# Pi_grammer_MAIN.net
KiCad netlist of a schematic drawn in EAGLE
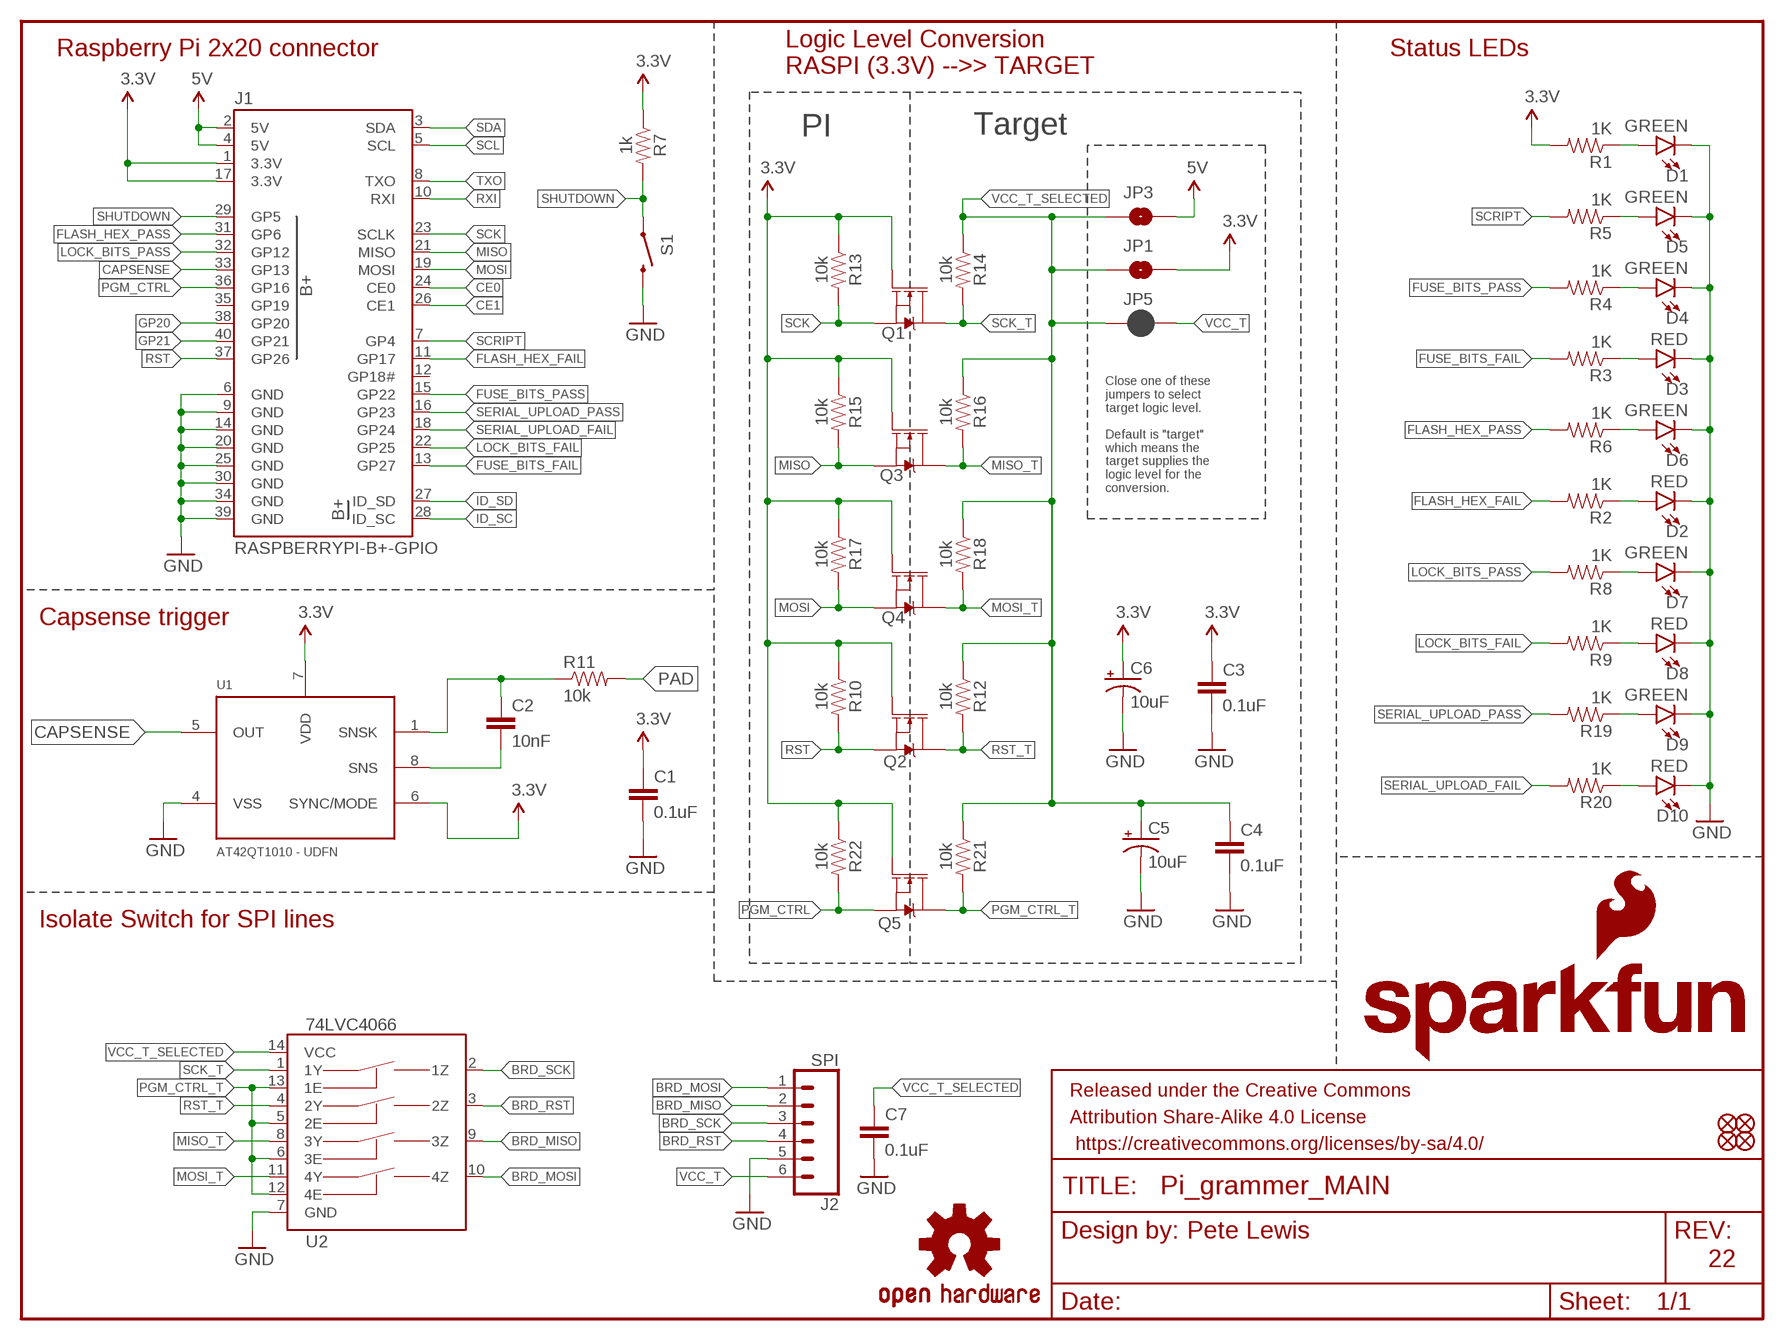
[diagram p0: schematic, sheet 1]

(export (version "E")
  (design (tool "Eeschema 10.0.6"))
  (components
    (comp (ref "C1")
      (value "0.1uF")
      (footprint "eagle-import:0603-CAP")
      (libsource (lib "eagle-import") (part "0.1UF-25V(+80/-20%)(0603)"))
    )
    (comp (ref "C2")
      (value "10nF")
      (footprint "eagle-import:0603-CAP")
      (libsource (lib "eagle-import") (part "10NF/10000PF-50V-10%(0603)"))
    )
    (comp (ref "C3")
      (value "0.1uF")
      (footprint "eagle-import:0603")
      (libsource (lib "eagle-import") (part "0.1UF-0603-25V-(+80/-20%)"))
    )
    (comp (ref "C4")
      (value "0.1uF")
      (footprint "eagle-import:0603")
      (libsource (lib "eagle-import") (part "0.1UF-0603-25V-(+80/-20%)"))
    )
    (comp (ref "C5")
      (value "10uF")
      (footprint "eagle-import:EIA3216")
      (libsource (lib "eagle-import") (part "10UF-POLAR-EIA3216-16V-10%(TANT)"))
    )
    (comp (ref "C6")
      (value "10uF")
      (footprint "eagle-import:EIA3216")
      (libsource (lib "eagle-import") (part "10UF-POLAR-EIA3216-16V-10%(TANT)"))
    )
    (comp (ref "C7")
      (value "0.1uF")
      (footprint "eagle-import:0603")
      (libsource (lib "eagle-import") (part "0.1UF-0603-25V-(+80/-20%)"))
    )
    (comp (ref "D1")
      (value "GREEN")
      (footprint "eagle-import:LED-1206")
      (libsource (lib "eagle-import") (part "LED-GREEN1206"))
    )
    (comp (ref "D2")
      (value "RED")
      (footprint "eagle-import:LED-1206")
      (libsource (lib "eagle-import") (part "LED-RED1206"))
    )
    (comp (ref "D3")
      (value "RED")
      (footprint "eagle-import:LED-1206")
      (libsource (lib "eagle-import") (part "LED-RED1206"))
    )
    (comp (ref "D4")
      (value "GREEN")
      (footprint "eagle-import:LED-1206")
      (libsource (lib "eagle-import") (part "LED-GREEN1206"))
    )
    (comp (ref "D5")
      (value "GREEN")
      (footprint "eagle-import:LED-1206")
      (libsource (lib "eagle-import") (part "LED-GREEN1206"))
    )
    (comp (ref "D6")
      (value "GREEN")
      (footprint "eagle-import:LED-1206")
      (libsource (lib "eagle-import") (part "LED-GREEN1206"))
    )
    (comp (ref "D7")
      (value "GREEN")
      (footprint "eagle-import:LED-1206")
      (libsource (lib "eagle-import") (part "LED-GREEN1206"))
    )
    (comp (ref "D8")
      (value "RED")
      (footprint "eagle-import:LED-1206")
      (libsource (lib "eagle-import") (part "LED-RED1206"))
    )
    (comp (ref "D9")
      (value "GREEN")
      (footprint "eagle-import:LED-1206")
      (libsource (lib "eagle-import") (part "LED-GREEN1206"))
    )
    (comp (ref "D10")
      (value "RED")
      (footprint "eagle-import:LED-1206")
      (libsource (lib "eagle-import") (part "LED-RED1206"))
    )
    (comp (ref "FD1")
      (value "FIDUCIALUFIDUCIAL")
      (footprint "eagle-import:FIDUCIAL-MICRO")
      (libsource (lib "eagle-import") (part "FIDUCIALUFIDUCIAL"))
    )
    (comp (ref "FD2")
      (value "FIDUCIALUFIDUCIAL")
      (footprint "eagle-import:FIDUCIAL-MICRO")
      (libsource (lib "eagle-import") (part "FIDUCIALUFIDUCIAL"))
    )
    (comp (ref "FD3")
      (value "FIDUCIALUFIDUCIAL")
      (footprint "eagle-import:FIDUCIAL-MICRO")
      (libsource (lib "eagle-import") (part "FIDUCIALUFIDUCIAL"))
    )
    (comp (ref "FD4")
      (value "FIDUCIALUFIDUCIAL")
      (footprint "eagle-import:FIDUCIAL-MICRO")
      (libsource (lib "eagle-import") (part "FIDUCIALUFIDUCIAL"))
    )
    (comp (ref "FRAME1")
      (value "FRAME-LETTER")
      (footprint "eagle-import:CREATIVE_COMMONS")
      (libsource (lib "eagle-import") (part "FRAME-LETTER"))
    )
    (comp (ref "J1")
      (value "RASPBERRYPI-B+-GPIO")
      (footprint "eagle-import:2X20-SHROUDED")
      (libsource (lib "eagle-import") (part "RASPBERRYPI-B+-GPIO"))
    )
    (comp (ref "J2")
      (value "SPI")
      (footprint "eagle-import:1X06-SMD_RA_MALE")
      (libsource (lib "eagle-import") (part "CONN_06SMD"))
    )
    (comp (ref "JP1")
      (value "JUMPER-SMT_2_NO_SILK")
      (footprint "eagle-import:SMT-JUMPER_2_NO_SILK")
      (libsource (lib "eagle-import") (part "JUMPER-SMT_2_NO_SILK"))
    )
    (comp (ref "JP3")
      (value "JUMPER-SMT_2_NO_SILK")
      (footprint "eagle-import:SMT-JUMPER_2_NO_SILK")
      (libsource (lib "eagle-import") (part "JUMPER-SMT_2_NO_SILK"))
    )
    (comp (ref "JP5")
      (value "JUMPER-SMT_2_NC_PASTE_SILK")
      (footprint "eagle-import:SMT-JUMPER_2_NC_PASTE_SILK")
      (libsource (lib "eagle-import") (part "JUMPER-SMT_2_NC_PASTE_SILK"))
    )
    (comp (ref "LOGO1")
      (value "SFE_LOGO_FLAME.2_INCH")
      (footprint "eagle-import:SFE_LOGO_FLAME_.2")
      (libsource (lib "eagle-import") (part "SFE_LOGO_FLAME.2_INCH"))
    )
    (comp (ref "LOGO2")
      (value "OSHW-LOGOL")
      (footprint "eagle-import:OSHW-LOGO-L")
      (libsource (lib "eagle-import") (part "OSHW-LOGOL"))
    )
    (comp (ref "LOGO3")
      (value "SFE_LOGO_NAME.6_INCH")
      (footprint "eagle-import:SFE_LOGO_NAME_.6")
      (libsource (lib "eagle-import") (part "SFE_LOGO_NAME.6_INCH"))
    )
    (comp (ref "Q1")
      (value "220mA/50V/3.5Ω")
      (footprint "eagle-import:SOT23-3")
      (libsource (lib "eagle-import") (part "MOSFET-NCH-BSS138"))
    )
    (comp (ref "Q2")
      (value "220mA/50V/3.5Ω")
      (footprint "eagle-import:SOT23-3")
      (libsource (lib "eagle-import") (part "MOSFET-NCH-BSS138"))
    )
    (comp (ref "Q3")
      (value "220mA/50V/3.5Ω")
      (footprint "eagle-import:SOT23-3")
      (libsource (lib "eagle-import") (part "MOSFET-NCH-BSS138"))
    )
    (comp (ref "Q4")
      (value "220mA/50V/3.5Ω")
      (footprint "eagle-import:SOT23-3")
      (libsource (lib "eagle-import") (part "MOSFET-NCH-BSS138"))
    )
    (comp (ref "Q5")
      (value "220mA/50V/3.5Ω")
      (footprint "eagle-import:SOT23-3")
      (libsource (lib "eagle-import") (part "MOSFET-NCH-BSS138"))
    )
    (comp (ref "R1")
      (value "1K")
      (footprint "eagle-import:0603-RES")
      (libsource (lib "eagle-import") (part "1KOHM-1/10W-1%(0603)"))
    )
    (comp (ref "R2")
      (value "1K")
      (footprint "eagle-import:0603-RES")
      (libsource (lib "eagle-import") (part "1KOHM-1/10W-1%(0603)"))
    )
    (comp (ref "R3")
      (value "1K")
      (footprint "eagle-import:0603-RES")
      (libsource (lib "eagle-import") (part "1KOHM-1/10W-1%(0603)"))
    )
    (comp (ref "R4")
      (value "1K")
      (footprint "eagle-import:0603-RES")
      (libsource (lib "eagle-import") (part "1KOHM-1/10W-1%(0603)"))
    )
    (comp (ref "R5")
      (value "1K")
      (footprint "eagle-import:0603-RES")
      (libsource (lib "eagle-import") (part "1KOHM-1/10W-1%(0603)"))
    )
    (comp (ref "R6")
      (value "1K")
      (footprint "eagle-import:0603-RES")
      (libsource (lib "eagle-import") (part "1KOHM-1/10W-1%(0603)"))
    )
    (comp (ref "R7")
      (value "1k")
      (footprint "eagle-import:0603")
      (libsource (lib "eagle-import") (part "1KOHM-0603-1/10W-1%"))
    )
    (comp (ref "R8")
      (value "1K")
      (footprint "eagle-import:0603-RES")
      (libsource (lib "eagle-import") (part "1KOHM-1/10W-1%(0603)"))
    )
    (comp (ref "R9")
      (value "1K")
      (footprint "eagle-import:0603-RES")
      (libsource (lib "eagle-import") (part "1KOHM-1/10W-1%(0603)"))
    )
    (comp (ref "R10")
      (value "10k")
      (footprint "eagle-import:0603")
      (libsource (lib "eagle-import") (part "10KOHM-0603-1/10W-1%"))
    )
    (comp (ref "R11")
      (value "10k")
      (footprint "eagle-import:0603-RES")
      (libsource (lib "eagle-import") (part "10KOHM-1/10W-1%(0603)0603"))
    )
    (comp (ref "R12")
      (value "10k")
      (footprint "eagle-import:0603")
      (libsource (lib "eagle-import") (part "10KOHM-0603-1/10W-1%"))
    )
    (comp (ref "R13")
      (value "10k")
      (footprint "eagle-import:0603")
      (libsource (lib "eagle-import") (part "10KOHM-0603-1/10W-1%"))
    )
    (comp (ref "R14")
      (value "10k")
      (footprint "eagle-import:0603")
      (libsource (lib "eagle-import") (part "10KOHM-0603-1/10W-1%"))
    )
    (comp (ref "R15")
      (value "10k")
      (footprint "eagle-import:0603")
      (libsource (lib "eagle-import") (part "10KOHM-0603-1/10W-1%"))
    )
    (comp (ref "R16")
      (value "10k")
      (footprint "eagle-import:0603")
      (libsource (lib "eagle-import") (part "10KOHM-0603-1/10W-1%"))
    )
    (comp (ref "R17")
      (value "10k")
      (footprint "eagle-import:0603")
      (libsource (lib "eagle-import") (part "10KOHM-0603-1/10W-1%"))
    )
    (comp (ref "R18")
      (value "10k")
      (footprint "eagle-import:0603")
      (libsource (lib "eagle-import") (part "10KOHM-0603-1/10W-1%"))
    )
    (comp (ref "R19")
      (value "1K")
      (footprint "eagle-import:0603-RES")
      (libsource (lib "eagle-import") (part "1KOHM-1/10W-1%(0603)"))
    )
    (comp (ref "R20")
      (value "1K")
      (footprint "eagle-import:0603-RES")
      (libsource (lib "eagle-import") (part "1KOHM-1/10W-1%(0603)"))
    )
    (comp (ref "R21")
      (value "10k")
      (footprint "eagle-import:0603")
      (libsource (lib "eagle-import") (part "10KOHM-0603-1/10W-1%"))
    )
    (comp (ref "R22")
      (value "10k")
      (footprint "eagle-import:0603")
      (libsource (lib "eagle-import") (part "10KOHM-0603-1/10W-1%"))
    )
    (comp (ref "S1")
      (value "SWITCH-MOMENTARY-2SMD")
      (footprint "eagle-import:TACTILE-SWITCH-SMD")
      (libsource (lib "eagle-import") (part "SWITCH-MOMENTARY-2SMD"))
    )
    (comp (ref "U1")
      (value "AT42QT1010 - UDFN")
      (footprint "eagle-import:UDFN_USON_8_PAD")
      (libsource (lib "eagle-import") (part "AT42QT1010UDFN"))
    )
    (comp (ref "U2")
      (value "74LVC4066")
      (footprint "eagle-import:SO14")
      (fields (field (name "PROD_ID") "IC-13944"))
      (libsource (lib "eagle-import") (part "74LVC4066D_QUAD_BILATERAL_SWITCH"))
    )
  )
  (nets
    (net (code "1") (name "3.3V") (class "Default")
      (node (ref "C1") (pin "1") (pinfunction "1_1") (pintype "passive"))
      (node (ref "C3") (pin "1") (pinfunction "1_1") (pintype "passive"))
      (node (ref "C6") (pin "+") (pinfunction "+_+") (pintype "passive"))
      (node (ref "J1") (pin "1") (pinfunction "3.3V_1") (pintype "power_in"))
      (node (ref "J1") (pin "17") (pinfunction "3.3V_17") (pintype "power_in"))
      (node (ref "JP1") (pin "2") (pinfunction "2_2") (pintype "passive"))
      (node (ref "Q1") (pin "1") (pinfunction "G_1") (pintype "bidirectional"))
      (node (ref "Q2") (pin "1") (pinfunction "G_1") (pintype "bidirectional"))
      (node (ref "Q3") (pin "1") (pinfunction "G_1") (pintype "bidirectional"))
      (node (ref "Q4") (pin "1") (pinfunction "G_1") (pintype "bidirectional"))
      (node (ref "Q5") (pin "1") (pinfunction "G_1") (pintype "bidirectional"))
      (node (ref "R1") (pin "2") (pinfunction "2_2") (pintype "passive"))
      (node (ref "R10") (pin "1") (pinfunction "1_1") (pintype "passive"))
      (node (ref "R13") (pin "1") (pinfunction "1_1") (pintype "passive"))
      (node (ref "R15") (pin "1") (pinfunction "1_1") (pintype "passive"))
      (node (ref "R17") (pin "1") (pinfunction "1_1") (pintype "passive"))
      (node (ref "R22") (pin "1") (pinfunction "1_1") (pintype "passive"))
      (node (ref "R7") (pin "1") (pinfunction "1_1") (pintype "passive"))
      (node (ref "U1") (pin "6") (pinfunction "SYNC/MODE_6") (pintype "bidirectional"))
      (node (ref "U1") (pin "7") (pinfunction "VDD_7") (pintype "bidirectional"))
    )
    (net (code "2") (name "5V") (class "Default")
      (node (ref "J1") (pin "2") (pinfunction "5V_2") (pintype "power_in"))
      (node (ref "J1") (pin "4") (pinfunction "5V_4") (pintype "power_in"))
      (node (ref "JP3") (pin "2") (pinfunction "2_2") (pintype "passive"))
    )
    (net (code "3") (name "BRD_MISO") (class "Default")
      (node (ref "J2") (pin "2") (pinfunction "2_2") (pintype "passive"))
      (node (ref "U2") (pin "9") (pinfunction "3Z_9") (pintype "bidirectional"))
    )
    (net (code "4") (name "BRD_MOSI") (class "Default")
      (node (ref "J2") (pin "1") (pinfunction "1_1") (pintype "passive"))
      (node (ref "U2") (pin "10") (pinfunction "4Z_10") (pintype "bidirectional"))
    )
    (net (code "5") (name "BRD_RST") (class "Default")
      (node (ref "J2") (pin "4") (pinfunction "4_4") (pintype "passive"))
      (node (ref "U2") (pin "3") (pinfunction "2Z_3") (pintype "bidirectional"))
    )
    (net (code "6") (name "BRD_SCK") (class "Default")
      (node (ref "J2") (pin "3") (pinfunction "3_3") (pintype "passive"))
      (node (ref "U2") (pin "2") (pinfunction "1Z_2") (pintype "bidirectional"))
    )
    (net (code "7") (name "CAPSENSE") (class "Default")
      (node (ref "J1") (pin "33") (pinfunction "GP13_33") (pintype "bidirectional"))
      (node (ref "U1") (pin "5") (pinfunction "OUT_5") (pintype "bidirectional"))
    )
    (net (code "8") (name "CE0") (class "Default")
      (node (ref "J1") (pin "24") (pinfunction "CE0_24") (pintype "output"))
    )
    (net (code "9") (name "CE1") (class "Default")
      (node (ref "J1") (pin "26") (pinfunction "CE1_26") (pintype "output"))
    )
    (net (code "10") (name "FLASH_HEX_FAIL") (class "Default")
      (node (ref "J1") (pin "11") (pinfunction "GP17_11") (pintype "bidirectional"))
      (node (ref "R2") (pin "2") (pinfunction "2_2") (pintype "passive"))
    )
    (net (code "11") (name "FLASH_HEX_PASS") (class "Default")
      (node (ref "J1") (pin "31") (pinfunction "GP6_31") (pintype "bidirectional"))
      (node (ref "R6") (pin "2") (pinfunction "2_2") (pintype "passive"))
    )
    (net (code "12") (name "FUSE_BITS_FAIL") (class "Default")
      (node (ref "J1") (pin "13") (pinfunction "GP27_13") (pintype "bidirectional"))
      (node (ref "R3") (pin "2") (pinfunction "2_2") (pintype "passive"))
    )
    (net (code "13") (name "FUSE_BITS_PASS") (class "Default")
      (node (ref "J1") (pin "15") (pinfunction "GP22_15") (pintype "bidirectional"))
      (node (ref "R4") (pin "2") (pinfunction "2_2") (pintype "passive"))
    )
    (net (code "14") (name "GND") (class "Default")
      (node (ref "C1") (pin "2") (pinfunction "2_2") (pintype "passive"))
      (node (ref "C3") (pin "2") (pinfunction "2_2") (pintype "passive"))
      (node (ref "C4") (pin "2") (pinfunction "2_2") (pintype "passive"))
      (node (ref "C5") (pin "-") (pinfunction "-_-") (pintype "passive"))
      (node (ref "C6") (pin "-") (pinfunction "-_-") (pintype "passive"))
      (node (ref "C7") (pin "2") (pinfunction "2_2") (pintype "passive"))
      (node (ref "D1") (pin "C") (pinfunction "C_C") (pintype "passive"))
      (node (ref "D10") (pin "C") (pinfunction "C_C") (pintype "passive"))
      (node (ref "D2") (pin "C") (pinfunction "C_C") (pintype "passive"))
      (node (ref "D3") (pin "C") (pinfunction "C_C") (pintype "passive"))
      (node (ref "D4") (pin "C") (pinfunction "C_C") (pintype "passive"))
      (node (ref "D5") (pin "C") (pinfunction "C_C") (pintype "passive"))
      (node (ref "D6") (pin "C") (pinfunction "C_C") (pintype "passive"))
      (node (ref "D7") (pin "C") (pinfunction "C_C") (pintype "passive"))
      (node (ref "D8") (pin "C") (pinfunction "C_C") (pintype "passive"))
      (node (ref "D9") (pin "C") (pinfunction "C_C") (pintype "passive"))
      (node (ref "J1") (pin "14") (pinfunction "GND_14") (pintype "power_in"))
      (node (ref "J1") (pin "20") (pinfunction "GND_20") (pintype "power_in"))
      (node (ref "J1") (pin "25") (pinfunction "GND_25") (pintype "power_in"))
      (node (ref "J1") (pin "30") (pinfunction "GND_30") (pintype "power_in"))
      (node (ref "J1") (pin "34") (pinfunction "GND_34") (pintype "power_in"))
      (node (ref "J1") (pin "39") (pinfunction "GND_39") (pintype "power_in"))
      (node (ref "J1") (pin "6") (pinfunction "GND_6") (pintype "power_in"))
      (node (ref "J1") (pin "9") (pinfunction "GND_9") (pintype "power_in"))
      (node (ref "J2") (pin "5") (pinfunction "5_5") (pintype "passive"))
      (node (ref "S1") (pin "3") (pinfunction "2_3") (pintype "passive"))
      (node (ref "U1") (pin "4") (pinfunction "VSS_4") (pintype "bidirectional"))
      (node (ref "U2") (pin "7") (pinfunction "GND_7") (pintype "bidirectional"))
    )
    (net (code "15") (name "GP20") (class "Default")
      (node (ref "J1") (pin "38") (pinfunction "GP20_38") (pintype "bidirectional"))
    )
    (net (code "16") (name "GP21") (class "Default")
      (node (ref "J1") (pin "40") (pinfunction "GP21_40") (pintype "bidirectional"))
    )
    (net (code "17") (name "ID_SC") (class "Default")
      (node (ref "J1") (pin "28") (pinfunction "ID_SC_28") (pintype "bidirectional"))
    )
    (net (code "18") (name "ID_SD") (class "Default")
      (node (ref "J1") (pin "27") (pinfunction "ID_SD_27") (pintype "bidirectional"))
    )
    (net (code "19") (name "LOCK_BITS_FAIL") (class "Default")
      (node (ref "J1") (pin "22") (pinfunction "GP25_22") (pintype "bidirectional"))
      (node (ref "R9") (pin "2") (pinfunction "2_2") (pintype "passive"))
    )
    (net (code "20") (name "LOCK_BITS_PASS") (class "Default")
      (node (ref "J1") (pin "32") (pinfunction "GP12_32") (pintype "bidirectional"))
      (node (ref "R8") (pin "2") (pinfunction "2_2") (pintype "passive"))
    )
    (net (code "21") (name "MISO") (class "Default")
      (node (ref "J1") (pin "21") (pinfunction "MISO_21") (pintype "input"))
      (node (ref "Q3") (pin "2") (pinfunction "S_2") (pintype "bidirectional"))
      (node (ref "R15") (pin "2") (pinfunction "2_2") (pintype "passive"))
    )
    (net (code "22") (name "MISO_T") (class "Default")
      (node (ref "Q3") (pin "3") (pinfunction "D_3") (pintype "bidirectional"))
      (node (ref "R16") (pin "2") (pinfunction "2_2") (pintype "passive"))
      (node (ref "U2") (pin "8") (pinfunction "3Y_8") (pintype "bidirectional"))
    )
    (net (code "23") (name "MOSI") (class "Default")
      (node (ref "J1") (pin "19") (pinfunction "MOSI_19") (pintype "output"))
      (node (ref "Q4") (pin "2") (pinfunction "S_2") (pintype "bidirectional"))
      (node (ref "R17") (pin "2") (pinfunction "2_2") (pintype "passive"))
    )
    (net (code "24") (name "MOSI_T") (class "Default")
      (node (ref "Q4") (pin "3") (pinfunction "D_3") (pintype "bidirectional"))
      (node (ref "R18") (pin "2") (pinfunction "2_2") (pintype "passive"))
      (node (ref "U2") (pin "11") (pinfunction "4Y_11") (pintype "bidirectional"))
    )
    (net (code "25") (name "Net-(D1-PadA)") (class "Default")
      (node (ref "D1") (pin "A") (pinfunction "A_A") (pintype "passive"))
      (node (ref "R1") (pin "1") (pinfunction "1_1") (pintype "passive"))
    )
    (net (code "26") (name "Net-(D2-PadA)") (class "Default")
      (node (ref "D2") (pin "A") (pinfunction "A_A") (pintype "passive"))
      (node (ref "R2") (pin "1") (pinfunction "1_1") (pintype "passive"))
    )
    (net (code "27") (name "Net-(D3-PadA)") (class "Default")
      (node (ref "D3") (pin "A") (pinfunction "A_A") (pintype "passive"))
      (node (ref "R3") (pin "1") (pinfunction "1_1") (pintype "passive"))
    )
    (net (code "28") (name "Net-(D4-PadA)") (class "Default")
      (node (ref "D4") (pin "A") (pinfunction "A_A") (pintype "passive"))
      (node (ref "R4") (pin "1") (pinfunction "1_1") (pintype "passive"))
    )
    (net (code "29") (name "Net-(D5-PadA)") (class "Default")
      (node (ref "D5") (pin "A") (pinfunction "A_A") (pintype "passive"))
      (node (ref "R5") (pin "1") (pinfunction "1_1") (pintype "passive"))
    )
    (net (code "30") (name "Net-(D6-PadA)") (class "Default")
      (node (ref "D6") (pin "A") (pinfunction "A_A") (pintype "passive"))
      (node (ref "R6") (pin "1") (pinfunction "1_1") (pintype "passive"))
    )
    (net (code "31") (name "Net-(D7-PadA)") (class "Default")
      (node (ref "D7") (pin "A") (pinfunction "A_A") (pintype "passive"))
      (node (ref "R8") (pin "1") (pinfunction "1_1") (pintype "passive"))
    )
    (net (code "32") (name "Net-(D8-PadA)") (class "Default")
      (node (ref "D8") (pin "A") (pinfunction "A_A") (pintype "passive"))
      (node (ref "R9") (pin "1") (pinfunction "1_1") (pintype "passive"))
    )
    (net (code "33") (name "Net-(D9-PadA)") (class "Default")
      (node (ref "D9") (pin "A") (pinfunction "A_A") (pintype "passive"))
      (node (ref "R19") (pin "1") (pinfunction "1_1") (pintype "passive"))
    )
    (net (code "34") (name "Net-(D10-PadA)") (class "Default")
      (node (ref "D10") (pin "A") (pinfunction "A_A") (pintype "passive"))
      (node (ref "R20") (pin "1") (pinfunction "1_1") (pintype "passive"))
    )
    (net (code "35") (name "Net-(U1-SNS)") (class "Default")
      (node (ref "C2") (pin "2") (pinfunction "2_2") (pintype "passive"))
      (node (ref "U1") (pin "8") (pinfunction "SNS_8") (pintype "bidirectional"))
    )
    (net (code "36") (name "Net-(U1-SNSK)") (class "Default")
      (node (ref "C2") (pin "1") (pinfunction "1_1") (pintype "passive"))
      (node (ref "R11") (pin "1") (pinfunction "1_1") (pintype "passive"))
      (node (ref "U1") (pin "1") (pinfunction "SNSK_1") (pintype "bidirectional"))
    )
    (net (code "37") (name "PAD") (class "Default")
      (node (ref "R11") (pin "2") (pinfunction "2_2") (pintype "passive"))
    )
    (net (code "38") (name "PGM_CTRL") (class "Default")
      (node (ref "J1") (pin "36") (pinfunction "GP16_36") (pintype "bidirectional"))
      (node (ref "Q5") (pin "2") (pinfunction "S_2") (pintype "bidirectional"))
      (node (ref "R22") (pin "2") (pinfunction "2_2") (pintype "passive"))
    )
    (net (code "39") (name "PGM_CTRL_T") (class "Default")
      (node (ref "Q5") (pin "3") (pinfunction "D_3") (pintype "bidirectional"))
      (node (ref "R21") (pin "2") (pinfunction "2_2") (pintype "passive"))
      (node (ref "U2") (pin "12") (pinfunction "4E_12") (pintype "bidirectional"))
      (node (ref "U2") (pin "13") (pinfunction "1E_13") (pintype "bidirectional"))
      (node (ref "U2") (pin "5") (pinfunction "2E_5") (pintype "bidirectional"))
      (node (ref "U2") (pin "6") (pinfunction "3E_6") (pintype "bidirectional"))
    )
    (net (code "40") (name "RST") (class "Default")
      (node (ref "J1") (pin "37") (pinfunction "GP26_37") (pintype "bidirectional"))
      (node (ref "Q2") (pin "2") (pinfunction "S_2") (pintype "bidirectional"))
      (node (ref "R10") (pin "2") (pinfunction "2_2") (pintype "passive"))
    )
    (net (code "41") (name "RST_T") (class "Default")
      (node (ref "Q2") (pin "3") (pinfunction "D_3") (pintype "bidirectional"))
      (node (ref "R12") (pin "2") (pinfunction "2_2") (pintype "passive"))
      (node (ref "U2") (pin "4") (pinfunction "2Y_4") (pintype "bidirectional"))
    )
    (net (code "42") (name "RXI") (class "Default")
      (node (ref "J1") (pin "10") (pinfunction "RXI_10") (pintype "input"))
    )
    (net (code "43") (name "SCK") (class "Default")
      (node (ref "J1") (pin "23") (pinfunction "SCLK_23") (pintype "output"))
      (node (ref "Q1") (pin "2") (pinfunction "S_2") (pintype "bidirectional"))
      (node (ref "R13") (pin "2") (pinfunction "2_2") (pintype "passive"))
    )
    (net (code "44") (name "SCK_T") (class "Default")
      (node (ref "Q1") (pin "3") (pinfunction "D_3") (pintype "bidirectional"))
      (node (ref "R14") (pin "2") (pinfunction "2_2") (pintype "passive"))
      (node (ref "U2") (pin "1") (pinfunction "1Y_1") (pintype "bidirectional"))
    )
    (net (code "45") (name "SCL") (class "Default")
      (node (ref "J1") (pin "5") (pinfunction "SCL_5") (pintype "bidirectional"))
    )
    (net (code "46") (name "SCRIPT") (class "Default")
      (node (ref "J1") (pin "7") (pinfunction "GP4_7") (pintype "bidirectional"))
      (node (ref "R5") (pin "2") (pinfunction "2_2") (pintype "passive"))
    )
    (net (code "47") (name "SDA") (class "Default")
      (node (ref "J1") (pin "3") (pinfunction "SDA_3") (pintype "bidirectional"))
    )
    (net (code "48") (name "SERIAL_UPLOAD_FAIL") (class "Default")
      (node (ref "J1") (pin "18") (pinfunction "GP24_18") (pintype "bidirectional"))
      (node (ref "R20") (pin "2") (pinfunction "2_2") (pintype "passive"))
    )
    (net (code "49") (name "SERIAL_UPLOAD_PASS") (class "Default")
      (node (ref "J1") (pin "16") (pinfunction "GP23_16") (pintype "bidirectional"))
      (node (ref "R19") (pin "2") (pinfunction "2_2") (pintype "passive"))
    )
    (net (code "50") (name "SHUTDOWN") (class "Default")
      (node (ref "J1") (pin "29") (pinfunction "GP5_29") (pintype "bidirectional"))
      (node (ref "R7") (pin "2") (pinfunction "2_2") (pintype "passive"))
      (node (ref "S1") (pin "1") (pinfunction "1_1") (pintype "passive"))
    )
    (net (code "51") (name "TXO") (class "Default")
      (node (ref "J1") (pin "8") (pinfunction "TXO_8") (pintype "output"))
    )
    (net (code "52") (name "VCC_T") (class "Default")
      (node (ref "J2") (pin "6") (pinfunction "6_6") (pintype "passive"))
      (node (ref "JP5") (pin "2") (pinfunction "2_2") (pintype "passive"))
    )
    (net (code "53") (name "VCC_T_SELECTED") (class "Default")
      (node (ref "C4") (pin "1") (pinfunction "1_1") (pintype "passive"))
      (node (ref "C5") (pin "+") (pinfunction "+_+") (pintype "passive"))
      (node (ref "C7") (pin "1") (pinfunction "1_1") (pintype "passive"))
      (node (ref "JP1") (pin "1") (pinfunction "1_1") (pintype "passive"))
      (node (ref "JP3") (pin "1") (pinfunction "1_1") (pintype "passive"))
      (node (ref "JP5") (pin "1") (pinfunction "1_1") (pintype "passive"))
      (node (ref "R12") (pin "1") (pinfunction "1_1") (pintype "passive"))
      (node (ref "R14") (pin "1") (pinfunction "1_1") (pintype "passive"))
      (node (ref "R16") (pin "1") (pinfunction "1_1") (pintype "passive"))
      (node (ref "R18") (pin "1") (pinfunction "1_1") (pintype "passive"))
      (node (ref "R21") (pin "1") (pinfunction "1_1") (pintype "passive"))
      (node (ref "U2") (pin "14") (pinfunction "VCC_14") (pintype "bidirectional"))
    )
    (net (code "54") (name "unconnected-(J1-GP18#-Pad12)") (class "Default")
      (node (ref "J1") (pin "12") (pinfunction "GP18#_12") (pintype "bidirectional"))
    )
    (net (code "55") (name "unconnected-(J1-GP19-Pad35)") (class "Default")
      (node (ref "J1") (pin "35") (pinfunction "GP19_35") (pintype "bidirectional"))
    )
  )
)
